# schematic_MUX_DEMUX.net
KiCad netlist of a schematic drawn in Altium Designer
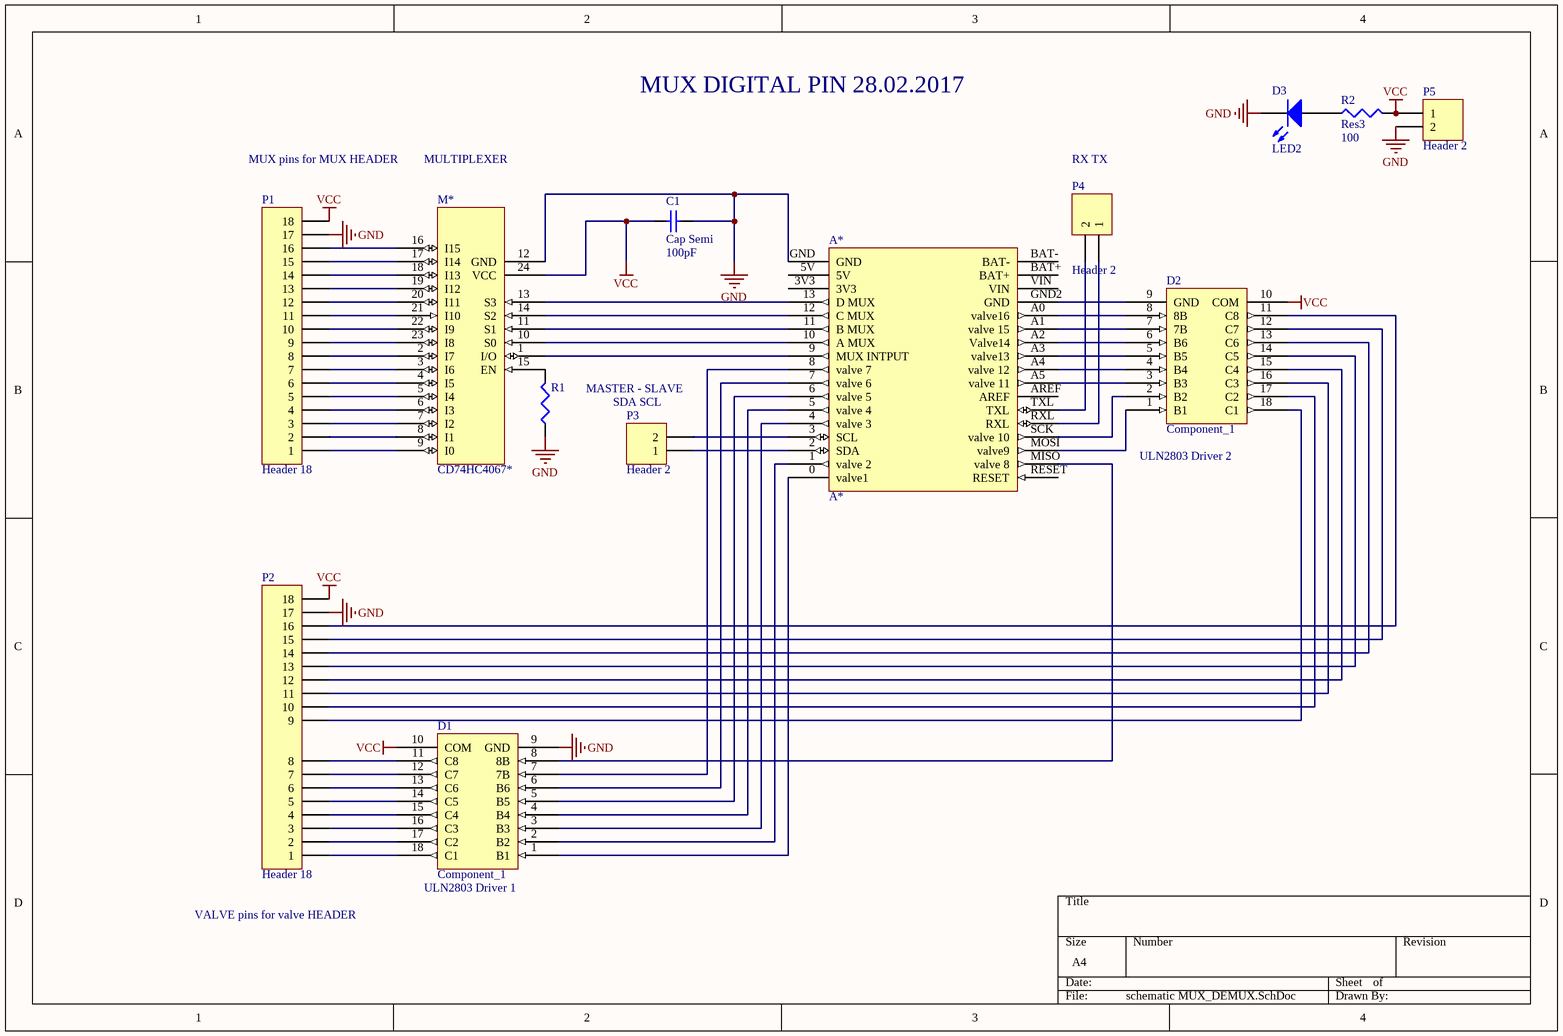
[diagram p0: schematic MUX_DEMUX.SchDoc]

(export (version "E")
  (design (tool "Eeschema 10.0.6"))
  (components
    (comp (ref "A*")
      (value "A*")
      (footprint "PCBComponent_1 - duplicate")
      (libsource (lib "Arduino pololu") (part "ARDUINO POLOLU"))
    )
    (comp (ref "C1")
      (value "Cap Semi")
      (footprint "C1206")
      (description "Capacitor (Semiconductor SIM Model)")
      (fields (field (name "ALTIUM_VALUE") "100pF") (field (name "PUBLISHER") "Altium Limited"))
      (libsource (lib "Miscellaneous Devices") (part "Cap Semi"))
    )
    (comp (ref "D1")
      (value "Component_1")
      (footprint "SOIC127P1030X265-18N")
      (libsource (lib "ULN2803A SOIC") (part "Component_1"))
    )
    (comp (ref "D2")
      (value "Component_1")
      (footprint "SOIC127P1030X265-18N")
      (libsource (lib "ULN2803A SOIC mirrored") (part "Component_1"))
    )
    (comp (ref "D3")
      (value "LED2")
      (footprint "3.2X1.6X1.1")
      (description "Typical RED, GREEN, YELLOW, AMBER GaAs LED")
      (fields (field (name "PUBLISHER") "Altium Limited"))
      (libsource (lib "Miscellaneous Devices") (part "LED2"))
    )
    (comp (ref "M*")
      (value "CD74HC4067*")
      (footprint "SOP65P780X200-24N")
      (description "analog mux/demux")
      (libsource (lib "CD74HC4067") (part "Component_1"))
    )
    (comp (ref "P1")
      (value "Header 18")
      (footprint "HDR1X18")
      (description "Header, 18-Pin")
      (fields (field (name "PUBLISHER") "Altium Limited"))
      (libsource (lib "Miscellaneous Connectors") (part "Header 18"))
    )
    (comp (ref "P2")
      (value "Header 18")
      (footprint "HDR1X20")
      (description "Header, 20-Pin")
      (fields (field (name "PUBLISHER") "Altium Limited"))
      (libsource (lib "Miscellaneous Connectors") (part "Header 20"))
    )
    (comp (ref "P3")
      (value "Header 2")
      (footprint "HDR1X2")
      (description "Header, 2-Pin")
      (fields (field (name "PUBLISHER") "Altium Limited"))
      (libsource (lib "") (part "Header 2_1"))
    )
    (comp (ref "P4")
      (value "Header 2")
      (footprint "HDR1X2")
      (description "Header, 2-Pin")
      (fields (field (name "PUBLISHER") "Altium Limited"))
      (libsource (lib "") (part "Header 2_2"))
    )
    (comp (ref "P5")
      (value "Header 2")
      (footprint "HDR1X2")
      (description "Header, 2-Pin")
      (fields (field (name "PUBLISHER") "Altium Limited"))
      (libsource (lib "Miscellaneous Connectors") (part "Header 2"))
    )
    (comp (ref "R1")
      (value "10K")
      (footprint "J1-0603")
      (description "Resistor")
      (fields (field (name "PUBLISHER") "Altium Limited"))
      (libsource (lib "Miscellaneous Devices") (part "Res3"))
    )
    (comp (ref "R2")
      (value "Res3")
      (footprint "J1-0603")
      (description "Resistor")
      (fields (field (name "ALTIUM_VALUE") "100") (field (name "PUBLISHER") "Altium Limited"))
      (libsource (lib "Miscellaneous Devices") (part "Res3"))
    )
  )
  (nets
    (net (code "1") (name "GND") (class "Default")
      (node (ref "A*") (pin "GND") (pinfunction "GND_GND") (pintype "power_in"))
      (node (ref "C1") (pin "2") (pinfunction "2_2") (pintype "passive"))
      (node (ref "D1") (pin "9") (pinfunction "GND_9") (pintype "power_in"))
      (node (ref "D3") (pin "2") (pinfunction "K_2") (pintype "passive"))
      (node (ref "M*") (pin "12") (pinfunction "GND_12") (pintype "power_in"))
      (node (ref "P1") (pin "17") (pinfunction "17_17") (pintype "passive"))
      (node (ref "P2") (pin "19") (pinfunction "17_19") (pintype "passive"))
      (node (ref "P5") (pin "2") (pinfunction "2_2") (pintype "passive"))
      (node (ref "R1") (pin "1") (pinfunction "1_1") (pintype "passive"))
    )
    (net (code "2") (name "Net-(A*-A_MUX)") (class "Default")
      (node (ref "A*") (pin "10") (pinfunction "A_MUX_10") (pintype "output"))
      (node (ref "M*") (pin "10") (pinfunction "S0_10") (pintype "input"))
    )
    (net (code "3") (name "Net-(A*-B_MUX)") (class "Default")
      (node (ref "A*") (pin "11") (pinfunction "B_MUX_11") (pintype "output"))
      (node (ref "M*") (pin "11") (pinfunction "S1_11") (pintype "input"))
    )
    (net (code "4") (name "Net-(A*-C_MUX)") (class "Default")
      (node (ref "A*") (pin "12") (pinfunction "C_MUX_12") (pintype "output"))
      (node (ref "M*") (pin "14") (pinfunction "S2_14") (pintype "input"))
    )
    (net (code "5") (name "Net-(A*-D_MUX)") (class "Default")
      (node (ref "A*") (pin "13") (pinfunction "D_MUX_13") (pintype "output"))
      (node (ref "M*") (pin "13") (pinfunction "S3_13") (pintype "input"))
    )
    (net (code "6") (name "Net-(A*-MUX_INTPUT)") (class "Default")
      (node (ref "A*") (pin "9") (pinfunction "MUX_INTPUT_9") (pintype "output"))
      (node (ref "M*") (pin "1") (pinfunction "I/O_1") (pintype "bidirectional"))
    )
    (net (code "7") (name "Net-(A*-PadRXL)") (class "Default")
      (node (ref "A*") (pin "RXL") (pinfunction "RXL_RXL") (pintype "bidirectional"))
      (node (ref "P4") (pin "1") (pinfunction "1_1") (pintype "passive"))
    )
    (net (code "8") (name "Net-(A*-PadTXL)") (class "Default")
      (node (ref "A*") (pin "TXL") (pinfunction "TXL_TXL") (pintype "bidirectional"))
      (node (ref "P4") (pin "2") (pinfunction "2_2") (pintype "passive"))
    )
    (net (code "9") (name "Net-(A*-SCL)") (class "Default")
      (node (ref "A*") (pin "3") (pinfunction "SCL_3") (pintype "bidirectional"))
      (node (ref "P3") (pin "2") (pinfunction "2_2") (pintype "passive"))
    )
    (net (code "10") (name "Net-(A*-SDA)") (class "Default")
      (node (ref "A*") (pin "2") (pinfunction "SDA_2") (pintype "bidirectional"))
      (node (ref "P3") (pin "1") (pinfunction "1_1") (pintype "passive"))
    )
    (net (code "11") (name "Net-(A*-Valve14)") (class "Default")
      (node (ref "A*") (pin "A2") (pinfunction "Valve14_A2") (pintype "output"))
      (node (ref "D2") (pin "6") (pinfunction "B6_6") (pintype "input"))
    )
    (net (code "12") (name "Net-(A*-valve1)") (class "Default")
      (node (ref "A*") (pin "0") (pinfunction "valve1_0") (pintype "passive"))
      (node (ref "D1") (pin "1") (pinfunction "B1_1") (pintype "input"))
    )
    (net (code "13") (name "Net-(A*-valve9)") (class "Default")
      (node (ref "A*") (pin "MOSI") (pinfunction "valve9_MOSI") (pintype "output"))
      (node (ref "D2") (pin "1") (pinfunction "B1_1") (pintype "input"))
    )
    (net (code "14") (name "Net-(A*-valve13)") (class "Default")
      (node (ref "A*") (pin "A3") (pinfunction "valve13_A3") (pintype "output"))
      (node (ref "D2") (pin "5") (pinfunction "B5_5") (pintype "input"))
    )
    (net (code "15") (name "Net-(A*-valve16)") (class "Default")
      (node (ref "A*") (pin "A0") (pinfunction "valve16_A0") (pintype "output"))
      (node (ref "D2") (pin "8") (pinfunction "8B_8") (pintype "input"))
    )
    (net (code "16") (name "Net-(A*-valve_2)") (class "Default")
      (node (ref "A*") (pin "1") (pinfunction "valve_2_1") (pintype "output"))
      (node (ref "D1") (pin "2") (pinfunction "B2_2") (pintype "input"))
    )
    (net (code "17") (name "Net-(A*-valve_3)") (class "Default")
      (node (ref "A*") (pin "4") (pinfunction "valve_3_4") (pintype "output"))
      (node (ref "D1") (pin "3") (pinfunction "B3_3") (pintype "input"))
    )
    (net (code "18") (name "Net-(A*-valve_4)") (class "Default")
      (node (ref "A*") (pin "5") (pinfunction "valve_4_5") (pintype "output"))
      (node (ref "D1") (pin "4") (pinfunction "B4_4") (pintype "input"))
    )
    (net (code "19") (name "Net-(A*-valve_5)") (class "Default")
      (node (ref "A*") (pin "6") (pinfunction "valve_5_6") (pintype "output"))
      (node (ref "D1") (pin "5") (pinfunction "B5_5") (pintype "input"))
    )
    (net (code "20") (name "Net-(A*-valve_6)") (class "Default")
      (node (ref "A*") (pin "7") (pinfunction "valve_6_7") (pintype "output"))
      (node (ref "D1") (pin "6") (pinfunction "B6_6") (pintype "input"))
    )
    (net (code "21") (name "Net-(A*-valve_7)") (class "Default")
      (node (ref "A*") (pin "8") (pinfunction "valve_7_8") (pintype "output"))
      (node (ref "D1") (pin "7") (pinfunction "7B_7") (pintype "input"))
    )
    (net (code "22") (name "Net-(A*-valve_8)") (class "Default")
      (node (ref "A*") (pin "MISO") (pinfunction "valve_8_MISO") (pintype "output"))
      (node (ref "D1") (pin "8") (pinfunction "8B_8") (pintype "input"))
    )
    (net (code "23") (name "Net-(A*-valve_10)") (class "Default")
      (node (ref "A*") (pin "SCK") (pinfunction "valve_10_SCK") (pintype "output"))
      (node (ref "D2") (pin "2") (pinfunction "B2_2") (pintype "input"))
    )
    (net (code "24") (name "Net-(A*-valve_11)") (class "Default")
      (node (ref "A*") (pin "A5") (pinfunction "valve_11_A5") (pintype "output"))
      (node (ref "D2") (pin "3") (pinfunction "B3_3") (pintype "input"))
    )
    (net (code "25") (name "Net-(A*-valve_12)") (class "Default")
      (node (ref "A*") (pin "A4") (pinfunction "valve_12_A4") (pintype "output"))
      (node (ref "D2") (pin "4") (pinfunction "B4_4") (pintype "input"))
    )
    (net (code "26") (name "Net-(A*-valve_15)") (class "Default")
      (node (ref "A*") (pin "A1") (pinfunction "valve_15_A1") (pintype "output"))
      (node (ref "D2") (pin "7") (pinfunction "7B_7") (pintype "input"))
    )
    (net (code "27") (name "Net-(D1-C1)") (class "Default")
      (node (ref "D1") (pin "18") (pinfunction "C1_18") (pintype "output"))
      (node (ref "P2") (pin "1") (pinfunction "1_1") (pintype "passive"))
    )
    (net (code "28") (name "Net-(D1-C2)") (class "Default")
      (node (ref "D1") (pin "17") (pinfunction "C2_17") (pintype "output"))
      (node (ref "P2") (pin "2") (pinfunction "2_2") (pintype "passive"))
    )
    (net (code "29") (name "Net-(D1-C3)") (class "Default")
      (node (ref "D1") (pin "16") (pinfunction "C3_16") (pintype "output"))
      (node (ref "P2") (pin "3") (pinfunction "3_3") (pintype "passive"))
    )
    (net (code "30") (name "Net-(D1-C4)") (class "Default")
      (node (ref "D1") (pin "15") (pinfunction "C4_15") (pintype "output"))
      (node (ref "P2") (pin "4") (pinfunction "4_4") (pintype "passive"))
    )
    (net (code "31") (name "Net-(D1-C5)") (class "Default")
      (node (ref "D1") (pin "14") (pinfunction "C5_14") (pintype "output"))
      (node (ref "P2") (pin "5") (pinfunction "5_5") (pintype "passive"))
    )
    (net (code "32") (name "Net-(D1-C6)") (class "Default")
      (node (ref "D1") (pin "13") (pinfunction "C6_13") (pintype "output"))
      (node (ref "P2") (pin "6") (pinfunction "6_6") (pintype "passive"))
    )
    (net (code "33") (name "Net-(D1-C7)") (class "Default")
      (node (ref "D1") (pin "12") (pinfunction "C7_12") (pintype "output"))
      (node (ref "P2") (pin "7") (pinfunction "7_7") (pintype "passive"))
    )
    (net (code "34") (name "Net-(D1-C8)") (class "Default")
      (node (ref "D1") (pin "11") (pinfunction "C8_11") (pintype "output"))
      (node (ref "P2") (pin "8") (pinfunction "8_8") (pintype "passive"))
    )
    (net (code "35") (name "Net-(D2-C1)") (class "Default")
      (node (ref "D2") (pin "18") (pinfunction "C1_18") (pintype "output"))
      (node (ref "P2") (pin "11") (pinfunction "9_11") (pintype "passive"))
    )
    (net (code "36") (name "Net-(D2-C2)") (class "Default")
      (node (ref "D2") (pin "17") (pinfunction "C2_17") (pintype "output"))
      (node (ref "P2") (pin "12") (pinfunction "10_12") (pintype "passive"))
    )
    (net (code "37") (name "Net-(D2-C3)") (class "Default")
      (node (ref "D2") (pin "16") (pinfunction "C3_16") (pintype "output"))
      (node (ref "P2") (pin "13") (pinfunction "11_13") (pintype "passive"))
    )
    (net (code "38") (name "Net-(D2-C4)") (class "Default")
      (node (ref "D2") (pin "15") (pinfunction "C4_15") (pintype "output"))
      (node (ref "P2") (pin "14") (pinfunction "12_14") (pintype "passive"))
    )
    (net (code "39") (name "Net-(D2-C5)") (class "Default")
      (node (ref "D2") (pin "14") (pinfunction "C5_14") (pintype "output"))
      (node (ref "P2") (pin "15") (pinfunction "13_15") (pintype "passive"))
    )
    (net (code "40") (name "Net-(D2-C6)") (class "Default")
      (node (ref "D2") (pin "13") (pinfunction "C6_13") (pintype "output"))
      (node (ref "P2") (pin "16") (pinfunction "14_16") (pintype "passive"))
    )
    (net (code "41") (name "Net-(D2-C7)") (class "Default")
      (node (ref "D2") (pin "12") (pinfunction "C7_12") (pintype "output"))
      (node (ref "P2") (pin "17") (pinfunction "15_17") (pintype "passive"))
    )
    (net (code "42") (name "Net-(D2-C8)") (class "Default")
      (node (ref "D2") (pin "11") (pinfunction "C8_11") (pintype "output"))
      (node (ref "P2") (pin "18") (pinfunction "16_18") (pintype "passive"))
    )
    (net (code "43") (name "Net-(D2-GND)") (class "Default")
      (node (ref "A*") (pin "GND2") (pinfunction "GND_GND2") (pintype "power_in"))
      (node (ref "D2") (pin "9") (pinfunction "GND_9") (pintype "power_in"))
    )
    (net (code "44") (name "Net-(D3-A)") (class "Default")
      (node (ref "D3") (pin "1") (pinfunction "A_1") (pintype "passive"))
      (node (ref "R2") (pin "1") (pinfunction "1_1") (pintype "passive"))
    )
    (net (code "45") (name "Net-(M*-EN)") (class "Default")
      (node (ref "M*") (pin "15") (pinfunction "EN_15") (pintype "input"))
      (node (ref "R1") (pin "2") (pinfunction "2_2") (pintype "passive"))
    )
    (net (code "46") (name "Net-(M*-I0)") (class "Default")
      (node (ref "M*") (pin "9") (pinfunction "I0_9") (pintype "bidirectional"))
      (node (ref "P1") (pin "1") (pinfunction "1_1") (pintype "passive"))
    )
    (net (code "47") (name "Net-(M*-I1)") (class "Default")
      (node (ref "M*") (pin "8") (pinfunction "I1_8") (pintype "bidirectional"))
      (node (ref "P1") (pin "2") (pinfunction "2_2") (pintype "passive"))
    )
    (net (code "48") (name "Net-(M*-I2)") (class "Default")
      (node (ref "M*") (pin "7") (pinfunction "I2_7") (pintype "bidirectional"))
      (node (ref "P1") (pin "3") (pinfunction "3_3") (pintype "passive"))
    )
    (net (code "49") (name "Net-(M*-I3)") (class "Default")
      (node (ref "M*") (pin "6") (pinfunction "I3_6") (pintype "bidirectional"))
      (node (ref "P1") (pin "4") (pinfunction "4_4") (pintype "passive"))
    )
    (net (code "50") (name "Net-(M*-I4)") (class "Default")
      (node (ref "M*") (pin "5") (pinfunction "I4_5") (pintype "bidirectional"))
      (node (ref "P1") (pin "5") (pinfunction "5_5") (pintype "passive"))
    )
    (net (code "51") (name "Net-(M*-I5)") (class "Default")
      (node (ref "M*") (pin "4") (pinfunction "I5_4") (pintype "bidirectional"))
      (node (ref "P1") (pin "6") (pinfunction "6_6") (pintype "passive"))
    )
    (net (code "52") (name "Net-(M*-I6)") (class "Default")
      (node (ref "M*") (pin "3") (pinfunction "I6_3") (pintype "bidirectional"))
      (node (ref "P1") (pin "7") (pinfunction "7_7") (pintype "passive"))
    )
    (net (code "53") (name "Net-(M*-I7)") (class "Default")
      (node (ref "M*") (pin "2") (pinfunction "I7_2") (pintype "bidirectional"))
      (node (ref "P1") (pin "8") (pinfunction "8_8") (pintype "passive"))
    )
    (net (code "54") (name "Net-(M*-I8)") (class "Default")
      (node (ref "M*") (pin "23") (pinfunction "I8_23") (pintype "bidirectional"))
      (node (ref "P1") (pin "9") (pinfunction "9_9") (pintype "passive"))
    )
    (net (code "55") (name "Net-(M*-I9)") (class "Default")
      (node (ref "M*") (pin "22") (pinfunction "I9_22") (pintype "bidirectional"))
      (node (ref "P1") (pin "10") (pinfunction "10_10") (pintype "passive"))
    )
    (net (code "56") (name "Net-(M*-I10)") (class "Default")
      (node (ref "M*") (pin "21") (pinfunction "I10_21") (pintype "input"))
      (node (ref "P1") (pin "11") (pinfunction "11_11") (pintype "passive"))
    )
    (net (code "57") (name "Net-(M*-I11)") (class "Default")
      (node (ref "M*") (pin "20") (pinfunction "I11_20") (pintype "bidirectional"))
      (node (ref "P1") (pin "12") (pinfunction "12_12") (pintype "passive"))
    )
    (net (code "58") (name "Net-(M*-I12)") (class "Default")
      (node (ref "M*") (pin "19") (pinfunction "I12_19") (pintype "bidirectional"))
      (node (ref "P1") (pin "13") (pinfunction "13_13") (pintype "passive"))
    )
    (net (code "59") (name "Net-(M*-I13)") (class "Default")
      (node (ref "M*") (pin "18") (pinfunction "I13_18") (pintype "bidirectional"))
      (node (ref "P1") (pin "14") (pinfunction "14_14") (pintype "passive"))
    )
    (net (code "60") (name "Net-(M*-I14)") (class "Default")
      (node (ref "M*") (pin "17") (pinfunction "I14_17") (pintype "bidirectional"))
      (node (ref "P1") (pin "15") (pinfunction "15_15") (pintype "passive"))
    )
    (net (code "61") (name "Net-(M*-I15)") (class "Default")
      (node (ref "M*") (pin "16") (pinfunction "I15_16") (pintype "bidirectional"))
      (node (ref "P1") (pin "16") (pinfunction "16_16") (pintype "passive"))
    )
    (net (code "62") (name "VCC") (class "Default")
      (node (ref "C1") (pin "1") (pinfunction "1_1") (pintype "passive"))
      (node (ref "D1") (pin "10") (pinfunction "COM_10") (pintype "power_in"))
      (node (ref "D2") (pin "10") (pinfunction "COM_10") (pintype "power_in"))
      (node (ref "M*") (pin "24") (pinfunction "VCC_24") (pintype "power_in"))
      (node (ref "P1") (pin "18") (pinfunction "18_18") (pintype "passive"))
      (node (ref "P2") (pin "20") (pinfunction "18_20") (pintype "passive"))
      (node (ref "P5") (pin "1") (pinfunction "1_1") (pintype "passive"))
      (node (ref "R2") (pin "2") (pinfunction "2_2") (pintype "passive"))
    )
    (net (code "63") (name "unconnected-(A*-Pad3V3)") (class "Default")
      (node (ref "A*") (pin "3V3") (pinfunction "3V3_3V3") (pintype "power_in"))
    )
    (net (code "64") (name "unconnected-(A*-Pad5V)") (class "Default")
      (node (ref "A*") (pin "5V") (pinfunction "5V_5V") (pintype "passive"))
    )
    (net (code "65") (name "unconnected-(A*-PadAREF)") (class "Default")
      (node (ref "A*") (pin "AREF") (pinfunction "AREF_AREF") (pintype "passive"))
    )
    (net (code "66") (name "unconnected-(A*-PadBAT+)") (class "Default")
      (node (ref "A*") (pin "BAT+") (pinfunction "BAT+_BAT+") (pintype "power_in"))
    )
    (net (code "67") (name "unconnected-(A*-PadBAT-)") (class "Default")
      (node (ref "A*") (pin "BAT-") (pinfunction "BAT-_BAT-") (pintype "passive"))
    )
    (net (code "68") (name "unconnected-(A*-PadRESET)") (class "Default")
      (node (ref "A*") (pin "RESET") (pinfunction "RESET_RESET") (pintype "input"))
    )
    (net (code "69") (name "unconnected-(A*-PadVIN)") (class "Default")
      (node (ref "A*") (pin "VIN") (pinfunction "VIN_VIN") (pintype "power_in"))
    )
  )
)
